# FilamentMonitor-1_0.net
KiCad netlist of a schematic drawn in EAGLE
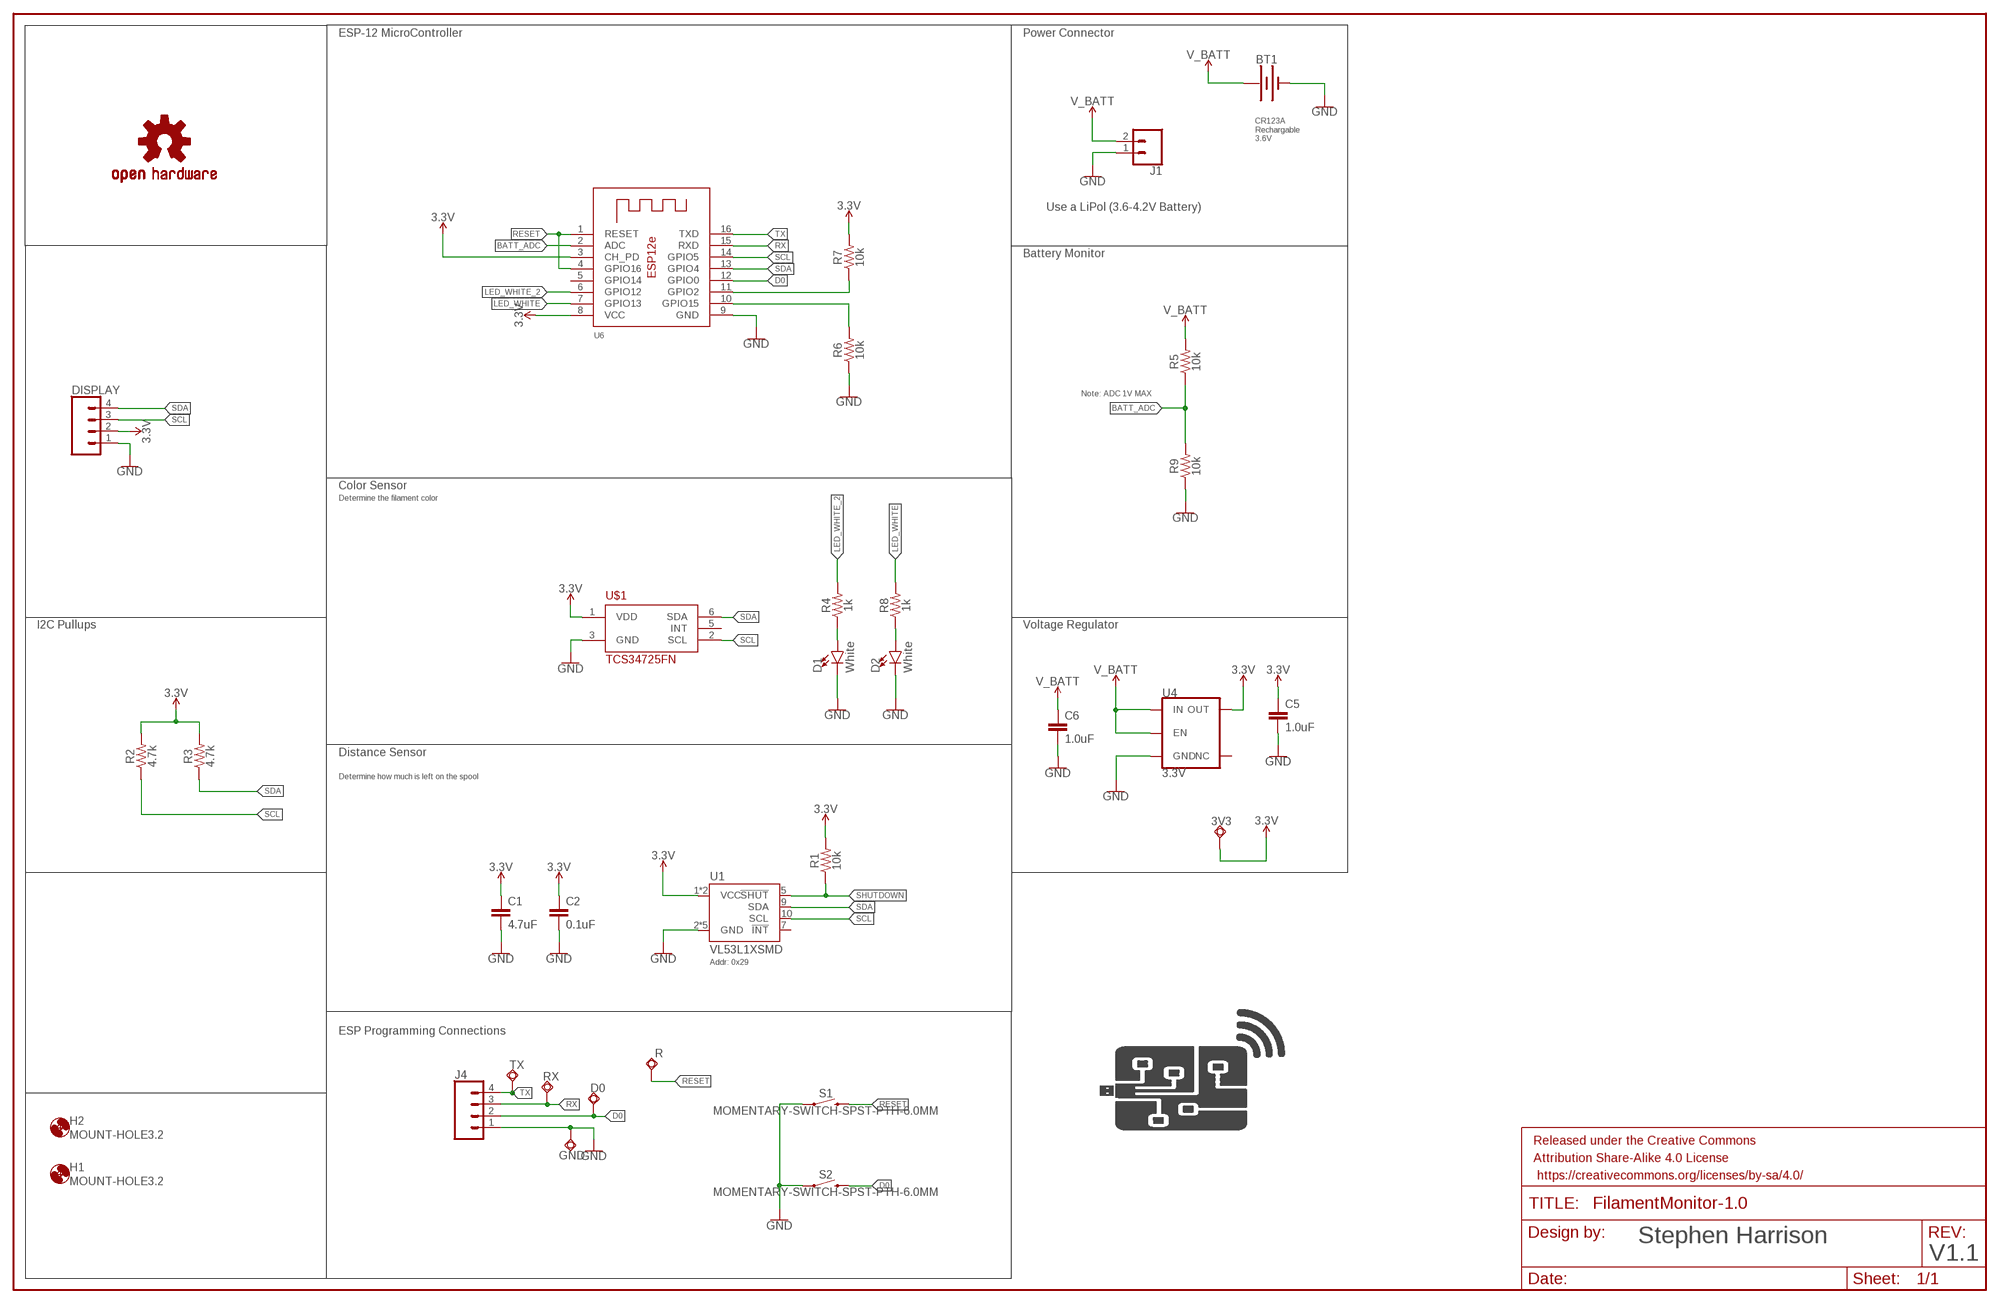
[diagram p0: schematic, sheet 1]

(export (version "E")
  (design (tool "Eeschema 10.0.6"))
  (components
    (comp (ref "3V3")
      (value "TPSQTP10SQ")
      (footprint "eagle-import:TP10SQ")
      (libsource (lib "eagle-import") (part "TPSQTP10SQ"))
    )
    (comp (ref "BT1")
      (value "BATTERY-16340")
      (footprint "eagle-import:BATTERY_16340-HOLDER")
      (libsource (lib "eagle-import") (part "BATTERY-16340"))
    )
    (comp (ref "C1")
      (value "4.7uF")
      (footprint "eagle-import:0603")
      (libsource (lib "eagle-import") (part "4.7UF-0603-6.3V-(10%)"))
    )
    (comp (ref "C2")
      (value "0.1uF")
      (footprint "eagle-import:0603")
      (libsource (lib "eagle-import") (part "0.1UF-0603-25V-5%"))
    )
    (comp (ref "C5")
      (value "1.0uF")
      (footprint "eagle-import:0603")
      (libsource (lib "eagle-import") (part "0.1UF-0603-25V-5%"))
    )
    (comp (ref "C6")
      (value "1.0uF")
      (footprint "eagle-import:0603")
      (libsource (lib "eagle-import") (part "0.1UF-0603-25V-5%"))
    )
    (comp (ref "D0")
      (value "TPSQTP10SQ")
      (footprint "eagle-import:TP10SQ")
      (libsource (lib "eagle-import") (part "TPSQTP10SQ"))
    )
    (comp (ref "D1")
      (value "White")
      (footprint "eagle-import:LED-1206")
      (libsource (lib "eagle-import") (part "LED-GREEN1206"))
    )
    (comp (ref "D2")
      (value "White")
      (footprint "eagle-import:LED-1206")
      (libsource (lib "eagle-import") (part "LED-GREEN1206"))
    )
    (comp (ref "DISPLAY")
      (value "CONN_04")
      (footprint "eagle-import:1X04")
      (libsource (lib "eagle-import") (part "CONN_04"))
    )
    (comp (ref "FRAME1")
      (value "FRAME-LEDGER")
      (footprint "eagle-import:CREATIVE_COMMONS")
      (libsource (lib "eagle-import") (part "FRAME-LEDGER"))
    )
    (comp (ref "GND")
      (value "TPSQTP10SQ")
      (footprint "eagle-import:TP10SQ")
      (libsource (lib "eagle-import") (part "TPSQTP10SQ"))
    )
    (comp (ref "H1")
      (value "MOUNT-HOLE3.2")
      (footprint "eagle-import:3,2")
      (libsource (lib "eagle-import") (part "MOUNT-HOLE3.2"))
    )
    (comp (ref "H2")
      (value "MOUNT-HOLE3.2")
      (footprint "eagle-import:3,2")
      (libsource (lib "eagle-import") (part "MOUNT-HOLE3.2"))
    )
    (comp (ref "J1")
      (value "CONN_02-JST-2MM-SMT")
      (footprint "eagle-import:JST-2-SMD")
      (libsource (lib "eagle-import") (part "CONN_02-JST-2MM-SMT"))
    )
    (comp (ref "J4")
      (value "CONN_04")
      (footprint "eagle-import:1X04")
      (libsource (lib "eagle-import") (part "CONN_04"))
    )
    (comp (ref "LOGO1")
      (value "OSHW-LOGOL")
      (footprint "eagle-import:OSHW-LOGO-L")
      (libsource (lib "eagle-import") (part "OSHW-LOGOL"))
    )
    (comp (ref "R")
      (value "TPSQTP10SQ")
      (footprint "eagle-import:TP10SQ")
      (libsource (lib "eagle-import") (part "TPSQTP10SQ"))
    )
    (comp (ref "R1")
      (value "10k")
      (footprint "eagle-import:0603")
      (libsource (lib "eagle-import") (part "10KOHM-0603-1/10W-1%"))
    )
    (comp (ref "R2")
      (value "4.7k")
      (footprint "eagle-import:0603")
      (libsource (lib "eagle-import") (part "4.7KOHM-0603-1/10W-1%"))
    )
    (comp (ref "R3")
      (value "4.7k")
      (footprint "eagle-import:0603")
      (libsource (lib "eagle-import") (part "4.7KOHM-0603-1/10W-1%"))
    )
    (comp (ref "R4")
      (value "1k")
      (footprint "eagle-import:0805")
      (libsource (lib "eagle-import") (part "RESISTOR0805"))
    )
    (comp (ref "R5")
      (value "10k")
      (footprint "eagle-import:0603")
      (libsource (lib "eagle-import") (part "10KOHM-0603-1/10W-1%"))
    )
    (comp (ref "R6")
      (value "10k")
      (footprint "eagle-import:0603")
      (libsource (lib "eagle-import") (part "10KOHM-0603-1/10W-1%"))
    )
    (comp (ref "R7")
      (value "10k")
      (footprint "eagle-import:0603")
      (libsource (lib "eagle-import") (part "10KOHM-0603-1/10W-1%"))
    )
    (comp (ref "R8")
      (value "1k")
      (footprint "eagle-import:0805")
      (libsource (lib "eagle-import") (part "RESISTOR0805"))
    )
    (comp (ref "R9")
      (value "10k")
      (footprint "eagle-import:0603")
      (libsource (lib "eagle-import") (part "10KOHM-0603-1/10W-1%"))
    )
    (comp (ref "RX")
      (value "TPSQTP10SQ")
      (footprint "eagle-import:TP10SQ")
      (libsource (lib "eagle-import") (part "TPSQTP10SQ"))
    )
    (comp (ref "S1")
      (value "MOMENTARY-SWITCH-SPST-PTH-6.0MM")
      (footprint "eagle-import:TACTILE_SWITCH_PTH_6.0MM")
      (libsource (lib "eagle-import") (part "MOMENTARY-SWITCH-SPST-PTH-6.0MM"))
    )
    (comp (ref "S2")
      (value "MOMENTARY-SWITCH-SPST-PTH-6.0MM")
      (footprint "eagle-import:TACTILE_SWITCH_PTH_6.0MM")
      (libsource (lib "eagle-import") (part "MOMENTARY-SWITCH-SPST-PTH-6.0MM"))
    )
    (comp (ref "TX")
      (value "TPSQTP10SQ")
      (footprint "eagle-import:TP10SQ")
      (libsource (lib "eagle-import") (part "TPSQTP10SQ"))
    )
    (comp (ref "U$1")
      (value "TCS34725FN")
      (footprint "eagle-import:FN-6")
      (libsource (lib "eagle-import") (part "TCS3472"))
    )
    (comp (ref "U$2")
      (value "THINGYSTICKS_LOGO")
      (footprint "eagle-import:THINGYSTICKS_LOGO")
      (libsource (lib "eagle-import") (part "THINGYSTICKS_LOGO"))
    )
    (comp (ref "U1")
      (value "VL53L1XSMD")
      (footprint "eagle-import:VL53L1X")
      (libsource (lib "eagle-import") (part "VL53L1XSMD"))
    )
    (comp (ref "U4")
      (value "3.3V")
      (footprint "eagle-import:SOT23-5")
      (libsource (lib "eagle-import") (part "V_REG_AP2112K-3.3V"))
    )
    (comp (ref "U6")
      (value "ESP-12E")
      (footprint "eagle-import:ESP-12E")
      (libsource (lib "eagle-import") (part "ESP-12E"))
    )
  )
  (nets
    (net (code "1") (name "3.3V") (class "Default")
      (node (ref "3V3") (pin "TP") (pinfunction "TP_TP") (pintype "input"))
      (node (ref "C1") (pin "1") (pinfunction "1_1") (pintype "passive"))
      (node (ref "C2") (pin "1") (pinfunction "1_1") (pintype "passive"))
      (node (ref "C5") (pin "1") (pinfunction "1_1") (pintype "passive"))
      (node (ref "DISPLAY") (pin "2") (pinfunction "2_2") (pintype "passive"))
      (node (ref "R1") (pin "2") (pinfunction "2_2") (pintype "passive"))
      (node (ref "R2") (pin "2") (pinfunction "2_2") (pintype "passive"))
      (node (ref "R3") (pin "2") (pinfunction "2_2") (pintype "passive"))
      (node (ref "R7") (pin "2") (pinfunction "2_2") (pintype "passive"))
      (node (ref "U$1") (pin "1") (pinfunction "VDD_1") (pintype "bidirectional"))
      (node (ref "U1") (pin "1") (pinfunction "VCC_1") (pintype "bidirectional"))
      (node (ref "U1") (pin "11") (pinfunction "VCC_11") (pintype "bidirectional"))
      (node (ref "U4") (pin "5") (pinfunction "OUT_5") (pintype "passive"))
      (node (ref "U6") (pin "3") (pinfunction "CH_PD_3") (pintype "input"))
      (node (ref "U6") (pin "8") (pinfunction "VCC_8") (pintype "power_in"))
    )
    (net (code "2") (name "BATT_ADC") (class "Default")
      (node (ref "R5") (pin "1") (pinfunction "1_1") (pintype "passive"))
      (node (ref "R9") (pin "2") (pinfunction "2_2") (pintype "passive"))
      (node (ref "U6") (pin "2") (pinfunction "ADC_2") (pintype "passive"))
    )
    (net (code "3") (name "D0") (class "Default")
      (node (ref "D0") (pin "TP") (pinfunction "TP_TP") (pintype "input"))
      (node (ref "J4") (pin "2") (pinfunction "2_2") (pintype "passive"))
      (node (ref "S2") (pin "3") (pinfunction "2_3") (pintype "passive"))
      (node (ref "U6") (pin "12") (pinfunction "GPIO0_12") (pintype "bidirectional"))
    )
    (net (code "4") (name "GND") (class "Default")
      (node (ref "BT1") (pin "P$2") (pinfunction "-_P$2") (pintype "power_in"))
      (node (ref "C1") (pin "2") (pinfunction "2_2") (pintype "passive"))
      (node (ref "C2") (pin "2") (pinfunction "2_2") (pintype "passive"))
      (node (ref "C5") (pin "2") (pinfunction "2_2") (pintype "passive"))
      (node (ref "C6") (pin "2") (pinfunction "2_2") (pintype "passive"))
      (node (ref "D1") (pin "C") (pinfunction "C_C") (pintype "passive"))
      (node (ref "D2") (pin "C") (pinfunction "C_C") (pintype "passive"))
      (node (ref "DISPLAY") (pin "1") (pinfunction "1_1") (pintype "passive"))
      (node (ref "GND") (pin "TP") (pinfunction "TP_TP") (pintype "input"))
      (node (ref "J1") (pin "1") (pinfunction "2_1") (pintype "passive"))
      (node (ref "J4") (pin "1") (pinfunction "1_1") (pintype "passive"))
      (node (ref "R6") (pin "1") (pinfunction "1_1") (pintype "passive"))
      (node (ref "R9") (pin "1") (pinfunction "1_1") (pintype "passive"))
      (node (ref "S1") (pin "1") (pinfunction "1_1") (pintype "passive"))
      (node (ref "S2") (pin "1") (pinfunction "1_1") (pintype "passive"))
      (node (ref "U$1") (pin "3") (pinfunction "GND_3") (pintype "bidirectional"))
      (node (ref "U1") (pin "12") (pinfunction "GND_12") (pintype "bidirectional"))
      (node (ref "U1") (pin "2") (pinfunction "GND_2") (pintype "bidirectional"))
      (node (ref "U1") (pin "3") (pinfunction "GND_3") (pintype "bidirectional"))
      (node (ref "U1") (pin "4") (pinfunction "GND_4") (pintype "bidirectional"))
      (node (ref "U1") (pin "6") (pinfunction "GND_6") (pintype "bidirectional"))
      (node (ref "U4") (pin "2") (pinfunction "GND_2") (pintype "input"))
      (node (ref "U6") (pin "9") (pinfunction "GND_9") (pintype "power_in"))
    )
    (net (code "5") (name "LED_WHITE") (class "Default")
      (node (ref "R8") (pin "2") (pinfunction "2_2") (pintype "passive"))
      (node (ref "U6") (pin "7") (pinfunction "GPIO13_7") (pintype "bidirectional"))
    )
    (net (code "6") (name "LED_WHITE_2") (class "Default")
      (node (ref "R4") (pin "2") (pinfunction "2_2") (pintype "passive"))
      (node (ref "U6") (pin "6") (pinfunction "GPIO12_6") (pintype "bidirectional"))
    )
    (net (code "7") (name "Net-(D1-PadA)") (class "Default")
      (node (ref "D1") (pin "A") (pinfunction "A_A") (pintype "passive"))
      (node (ref "R4") (pin "1") (pinfunction "1_1") (pintype "passive"))
    )
    (net (code "8") (name "Net-(D2-PadA)") (class "Default")
      (node (ref "D2") (pin "A") (pinfunction "A_A") (pintype "passive"))
      (node (ref "R8") (pin "1") (pinfunction "1_1") (pintype "passive"))
    )
    (net (code "9") (name "Net-(U6-GPIO2)") (class "Default")
      (node (ref "R7") (pin "1") (pinfunction "1_1") (pintype "passive"))
      (node (ref "U6") (pin "11") (pinfunction "GPIO2_11") (pintype "bidirectional"))
    )
    (net (code "10") (name "Net-(U6-GPIO15)") (class "Default")
      (node (ref "R6") (pin "2") (pinfunction "2_2") (pintype "passive"))
      (node (ref "U6") (pin "10") (pinfunction "GPIO15_10") (pintype "bidirectional"))
    )
    (net (code "11") (name "RESET") (class "Default")
      (node (ref "R") (pin "TP") (pinfunction "TP_TP") (pintype "input"))
      (node (ref "S1") (pin "3") (pinfunction "2_3") (pintype "passive"))
      (node (ref "U6") (pin "1") (pinfunction "RESET_1") (pintype "input"))
      (node (ref "U6") (pin "4") (pinfunction "GPIO16_4") (pintype "bidirectional"))
    )
    (net (code "12") (name "RX") (class "Default")
      (node (ref "J4") (pin "3") (pinfunction "3_3") (pintype "passive"))
      (node (ref "RX") (pin "TP") (pinfunction "TP_TP") (pintype "input"))
      (node (ref "U6") (pin "15") (pinfunction "RXD_15") (pintype "input"))
    )
    (net (code "13") (name "SCL") (class "Default")
      (node (ref "DISPLAY") (pin "3") (pinfunction "3_3") (pintype "passive"))
      (node (ref "R2") (pin "1") (pinfunction "1_1") (pintype "passive"))
      (node (ref "U$1") (pin "2") (pinfunction "SCL_2") (pintype "bidirectional"))
      (node (ref "U1") (pin "10") (pinfunction "SCL_10") (pintype "bidirectional"))
      (node (ref "U6") (pin "14") (pinfunction "GPIO5_14") (pintype "bidirectional"))
    )
    (net (code "14") (name "SDA") (class "Default")
      (node (ref "DISPLAY") (pin "4") (pinfunction "4_4") (pintype "passive"))
      (node (ref "R3") (pin "1") (pinfunction "1_1") (pintype "passive"))
      (node (ref "U$1") (pin "6") (pinfunction "SDA_6") (pintype "bidirectional"))
      (node (ref "U1") (pin "9") (pinfunction "SDA_9") (pintype "bidirectional"))
      (node (ref "U6") (pin "13") (pinfunction "GPIO4_13") (pintype "bidirectional"))
    )
    (net (code "15") (name "SHUTDOWN") (class "Default")
      (node (ref "R1") (pin "1") (pinfunction "1_1") (pintype "passive"))
      (node (ref "U1") (pin "5") (pinfunction "~{SHUT}_5") (pintype "bidirectional"))
    )
    (net (code "16") (name "TX") (class "Default")
      (node (ref "J4") (pin "4") (pinfunction "4_4") (pintype "passive"))
      (node (ref "TX") (pin "TP") (pinfunction "TP_TP") (pintype "input"))
      (node (ref "U6") (pin "16") (pinfunction "TXD_16") (pintype "output"))
    )
    (net (code "17") (name "V_BATT") (class "Default")
      (node (ref "BT1") (pin "P$1") (pinfunction "+_P$1") (pintype "power_in"))
      (node (ref "C6") (pin "1") (pinfunction "1_1") (pintype "passive"))
      (node (ref "J1") (pin "2") (pinfunction "1_2") (pintype "passive"))
      (node (ref "R5") (pin "2") (pinfunction "2_2") (pintype "passive"))
      (node (ref "U4") (pin "1") (pinfunction "IN_1") (pintype "input"))
      (node (ref "U4") (pin "3") (pinfunction "EN_3") (pintype "input"))
    )
    (net (code "18") (name "unconnected-(U$1-INT-Pad5)") (class "Default")
      (node (ref "U$1") (pin "5") (pinfunction "INT_5") (pintype "bidirectional"))
    )
    (net (code "19") (name "unconnected-(U1-~{INT}-Pad7)") (class "Default")
      (node (ref "U1") (pin "7") (pinfunction "~{INT}_7") (pintype "bidirectional"))
    )
    (net (code "20") (name "unconnected-(U4-NC-Pad4)") (class "Default")
      (node (ref "U4") (pin "4") (pinfunction "NC_4") (pintype "no_connect"))
    )
    (net (code "21") (name "unconnected-(U6-GPIO14-Pad5)") (class "Default")
      (node (ref "U6") (pin "5") (pinfunction "GPIO14_5") (pintype "bidirectional"))
    )
  )
)
